# nm_usb.net
KiCad netlist of a schematic drawn in Altium Designer
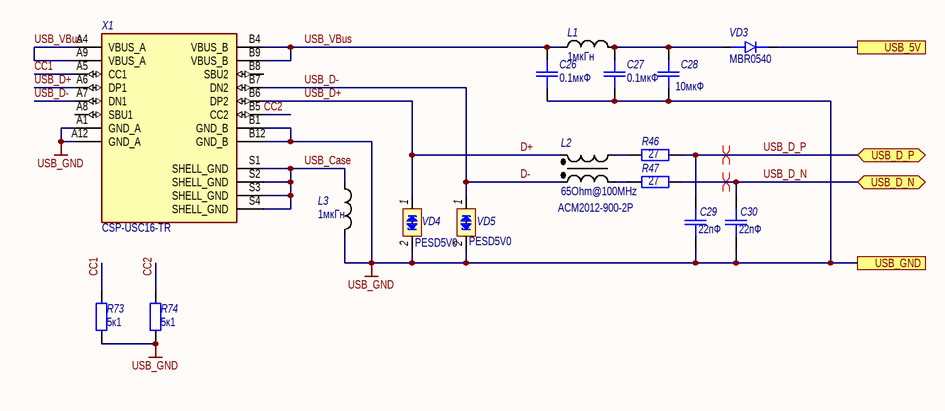
[diagram p0: nm_usb.SchDoc]

(export (version "E")
  (design (tool "Eeschema 10.0.6"))
  (components
    (comp (ref "C26")
      (value "0.1мкФ")
      (footprint "SMD_C0603")
      (description "Capacitor")
      (libsource (lib "Passive") (part "Capacitor"))
    )
    (comp (ref "C27")
      (value "0.1мкФ")
      (footprint "SMD_C0603")
      (description "Capacitor")
      (libsource (lib "Passive") (part "Capacitor"))
    )
    (comp (ref "C28")
      (value "10мкФ")
      (footprint "SMD_C0603")
      (description "Capacitor")
      (libsource (lib "Passive") (part "Capacitor"))
    )
    (comp (ref "C29")
      (value "22пФ")
      (footprint "SMD_C0603")
      (description "Capacitor")
      (fields (field (name "Comment") "K10-79"))
      (libsource (lib "Passive") (part "Capacitor"))
    )
    (comp (ref "C30")
      (value "22пФ")
      (footprint "SMD_C0603")
      (description "Capacitor")
      (fields (field (name "Comment") "K10-79"))
      (libsource (lib "Passive") (part "Capacitor"))
    )
    (comp (ref "L1")
      (value "1мкГн")
      (footprint "SMD_0805")
      (description "Inductor")
      (libsource (lib "Passive") (part "Inductor"))
    )
    (comp (ref "L2")
      (value "65Ohm@100MHz")
      (footprint "ACM2012")
      (description "Coupled inductor")
      (fields (field (name "НАИМЕНОВАНИЕ") "ACM2012-900-2P"))
      (libsource (lib "Passive") (part "Inductor_coupled"))
    )
    (comp (ref "L3")
      (value "1мкГн")
      (footprint "SMD_0805")
      (description "Inductor")
      (libsource (lib "Passive") (part "Inductor"))
    )
    (comp (ref "R46")
      (value "27")
      (footprint "SMD_0603")
      (description "Resistor")
      (fields (field (name "Comment") "OSM R1-8"))
      (libsource (lib "") (part "Resistor_2"))
    )
    (comp (ref "R47")
      (value "27")
      (footprint "SMD_0603")
      (description "Resistor")
      (fields (field (name "Comment") "OSM R1-8"))
      (libsource (lib "") (part "Resistor_2"))
    )
    (comp (ref "R73")
      (value "5к1")
      (footprint "SMD_0603")
      (description "Resistor")
      (fields (field (name "Comment") "OSM R1-8"))
      (libsource (lib "") (part "Resistor_1"))
    )
    (comp (ref "R74")
      (value "5к1")
      (footprint "SMD_0603")
      (description "Resistor")
      (fields (field (name "Comment") "OSM R1-8"))
      (libsource (lib "Passive") (part "Resistor"))
    )
    (comp (ref "VD3")
      (value "MBR0540")
      (footprint "SOD-123")
      (description "Schottky diode")
      (fields (field (name "НАИМЕНОВАНИЕ") "MBR0540"))
      (libsource (lib "Diod") (part "MBR0540"))
    )
    (comp (ref "VD4")
      (value "PESD5V0")
      (footprint "SOD-323")
      (description "Low capacitance bidirectional ESD protection diodes")
      (libsource (lib "Diod") (part "PESDxL1BA"))
    )
    (comp (ref "VD5")
      (value "PESD5V0")
      (footprint "SOD-323")
      (description "Low capacitance bidirectional ESD protection diodes")
      (libsource (lib "Diod") (part "PESDxL1BA"))
    )
    (comp (ref "X1")
      (value "CSP-USC16-TR")
      (footprint "VALCON_CSP-USC16-TR")
      (description "CSP-USC16-TR Valcon USB Type C Surface Mount PCB Socket")
      (fields (field (name "MF") "Valcon") (field (name "НАИМЕНОВАНИЕ") "CSP-USC16-TR"))
      (libsource (lib "CSP-USC16-TR") (part "CSP-USC16-TR"))
    )
  )
  (nets
    (net (code "1") (name "/D+") (class "Default")
      (node (ref "L2") (pin "3") (pinfunction "3_3") (pintype "passive"))
      (node (ref "VD4") (pin "1") (pinfunction "cathode_1_1") (pintype "passive"))
      (node (ref "X1") (pin "A6") (pinfunction "DP1_A6") (pintype "bidirectional"))
      (node (ref "X1") (pin "B6") (pinfunction "DP2_B6") (pintype "bidirectional"))
    )
    (net (code "2") (name "/D-") (class "Default")
      (node (ref "L2") (pin "2") (pinfunction "2_2") (pintype "passive"))
      (node (ref "VD5") (pin "1") (pinfunction "cathode_1_1") (pintype "passive"))
      (node (ref "X1") (pin "A7") (pinfunction "DN1_A7") (pintype "bidirectional"))
      (node (ref "X1") (pin "B7") (pinfunction "DN2_B7") (pintype "bidirectional"))
    )
    (net (code "3") (name "/USB_5V") (class "Default")
      (node (ref "VD3") (pin "1") (pinfunction "Cathode_1") (pintype "passive"))
    )
    (net (code "4") (name "/USB_Case") (class "Default")
      (node (ref "L3") (pin "1") (pinfunction "1_1") (pintype "passive"))
      (node (ref "X1") (pin "S1") (pinfunction "SHELL_GND_S1") (pintype "power_in"))
      (node (ref "X1") (pin "S2") (pinfunction "SHELL_GND_S2") (pintype "power_in"))
      (node (ref "X1") (pin "S3") (pinfunction "SHELL_GND_S3") (pintype "power_in"))
      (node (ref "X1") (pin "S4") (pinfunction "SHELL_GND_S4") (pintype "power_in"))
    )
    (net (code "5") (name "/USB_D_N") (class "Default")
      (node (ref "C30") (pin "2") (pinfunction "2_2") (pintype "passive"))
      (node (ref "R47") (pin "2") (pinfunction "2_2") (pintype "passive"))
    )
    (net (code "6") (name "/USB_D_P") (class "Default")
      (node (ref "C29") (pin "2") (pinfunction "2_2") (pintype "passive"))
      (node (ref "R46") (pin "2") (pinfunction "2_2") (pintype "passive"))
    )
    (net (code "7") (name "/USB_VBus") (class "Default")
      (node (ref "C26") (pin "2") (pinfunction "2_2") (pintype "passive"))
      (node (ref "L1") (pin "1") (pinfunction "1_1") (pintype "passive"))
      (node (ref "X1") (pin "A4") (pinfunction "VBUS_A_A4") (pintype "power_in"))
      (node (ref "X1") (pin "A9") (pinfunction "VBUS_A_A9") (pintype "power_in"))
      (node (ref "X1") (pin "B4") (pinfunction "VBUS_B_B4") (pintype "power_in"))
      (node (ref "X1") (pin "B9") (pinfunction "VBUS_B_B9") (pintype "power_in"))
    )
    (net (code "8") (name "/СС1") (class "Default")
      (node (ref "R73") (pin "1") (pinfunction "1_1") (pintype "passive"))
      (node (ref "X1") (pin "A5") (pinfunction "CC1_A5") (pintype "bidirectional"))
    )
    (net (code "9") (name "/СС2") (class "Default")
      (node (ref "R74") (pin "2") (pinfunction "2_2") (pintype "passive"))
      (node (ref "X1") (pin "B5") (pinfunction "CC2_B5") (pintype "bidirectional"))
    )
    (net (code "10") (name "Net-(L2-Pad1)") (class "Default")
      (node (ref "L2") (pin "1") (pinfunction "1_1") (pintype "passive"))
      (node (ref "R47") (pin "1") (pinfunction "1_1") (pintype "passive"))
    )
    (net (code "11") (name "Net-(L2-Pad4)") (class "Default")
      (node (ref "L2") (pin "4") (pinfunction "4_4") (pintype "passive"))
      (node (ref "R46") (pin "1") (pinfunction "1_1") (pintype "passive"))
    )
    (net (code "12") (name "Net-(VD3-Anode)") (class "Default")
      (node (ref "C27") (pin "2") (pinfunction "2_2") (pintype "passive"))
      (node (ref "C28") (pin "2") (pinfunction "2_2") (pintype "passive"))
      (node (ref "L1") (pin "2") (pinfunction "2_2") (pintype "passive"))
      (node (ref "VD3") (pin "2") (pinfunction "Anode_2") (pintype "passive"))
    )
    (net (code "13") (name "USB_GND") (class "Default")
      (node (ref "C26") (pin "1") (pinfunction "1_1") (pintype "passive"))
      (node (ref "C27") (pin "1") (pinfunction "1_1") (pintype "passive"))
      (node (ref "C28") (pin "1") (pinfunction "1_1") (pintype "passive"))
      (node (ref "C29") (pin "1") (pinfunction "1_1") (pintype "passive"))
      (node (ref "C30") (pin "1") (pinfunction "1_1") (pintype "passive"))
      (node (ref "L3") (pin "2") (pinfunction "2_2") (pintype "passive"))
      (node (ref "R73") (pin "2") (pinfunction "2_2") (pintype "passive"))
      (node (ref "R74") (pin "1") (pinfunction "1_1") (pintype "passive"))
      (node (ref "VD4") (pin "2") (pinfunction "cathode_2_2") (pintype "passive"))
      (node (ref "VD5") (pin "2") (pinfunction "cathode_2_2") (pintype "passive"))
      (node (ref "X1") (pin "A1") (pinfunction "GND_A_A1") (pintype "power_in"))
      (node (ref "X1") (pin "A12") (pinfunction "GND_A_A12") (pintype "power_in"))
      (node (ref "X1") (pin "B1") (pinfunction "GND_B_B1") (pintype "power_in"))
      (node (ref "X1") (pin "B12") (pinfunction "GND_B_B12") (pintype "power_in"))
    )
    (net (code "14") (name "unconnected-(X1-SBU1-PadA8)") (class "Default")
      (node (ref "X1") (pin "A8") (pinfunction "SBU1_A8") (pintype "bidirectional"))
    )
    (net (code "15") (name "unconnected-(X1-SBU2-PadB8)") (class "Default")
      (node (ref "X1") (pin "B8") (pinfunction "SBU2_B8") (pintype "bidirectional"))
    )
  )
)
